# main.net
KiCad netlist of a schematic drawn in EAGLE
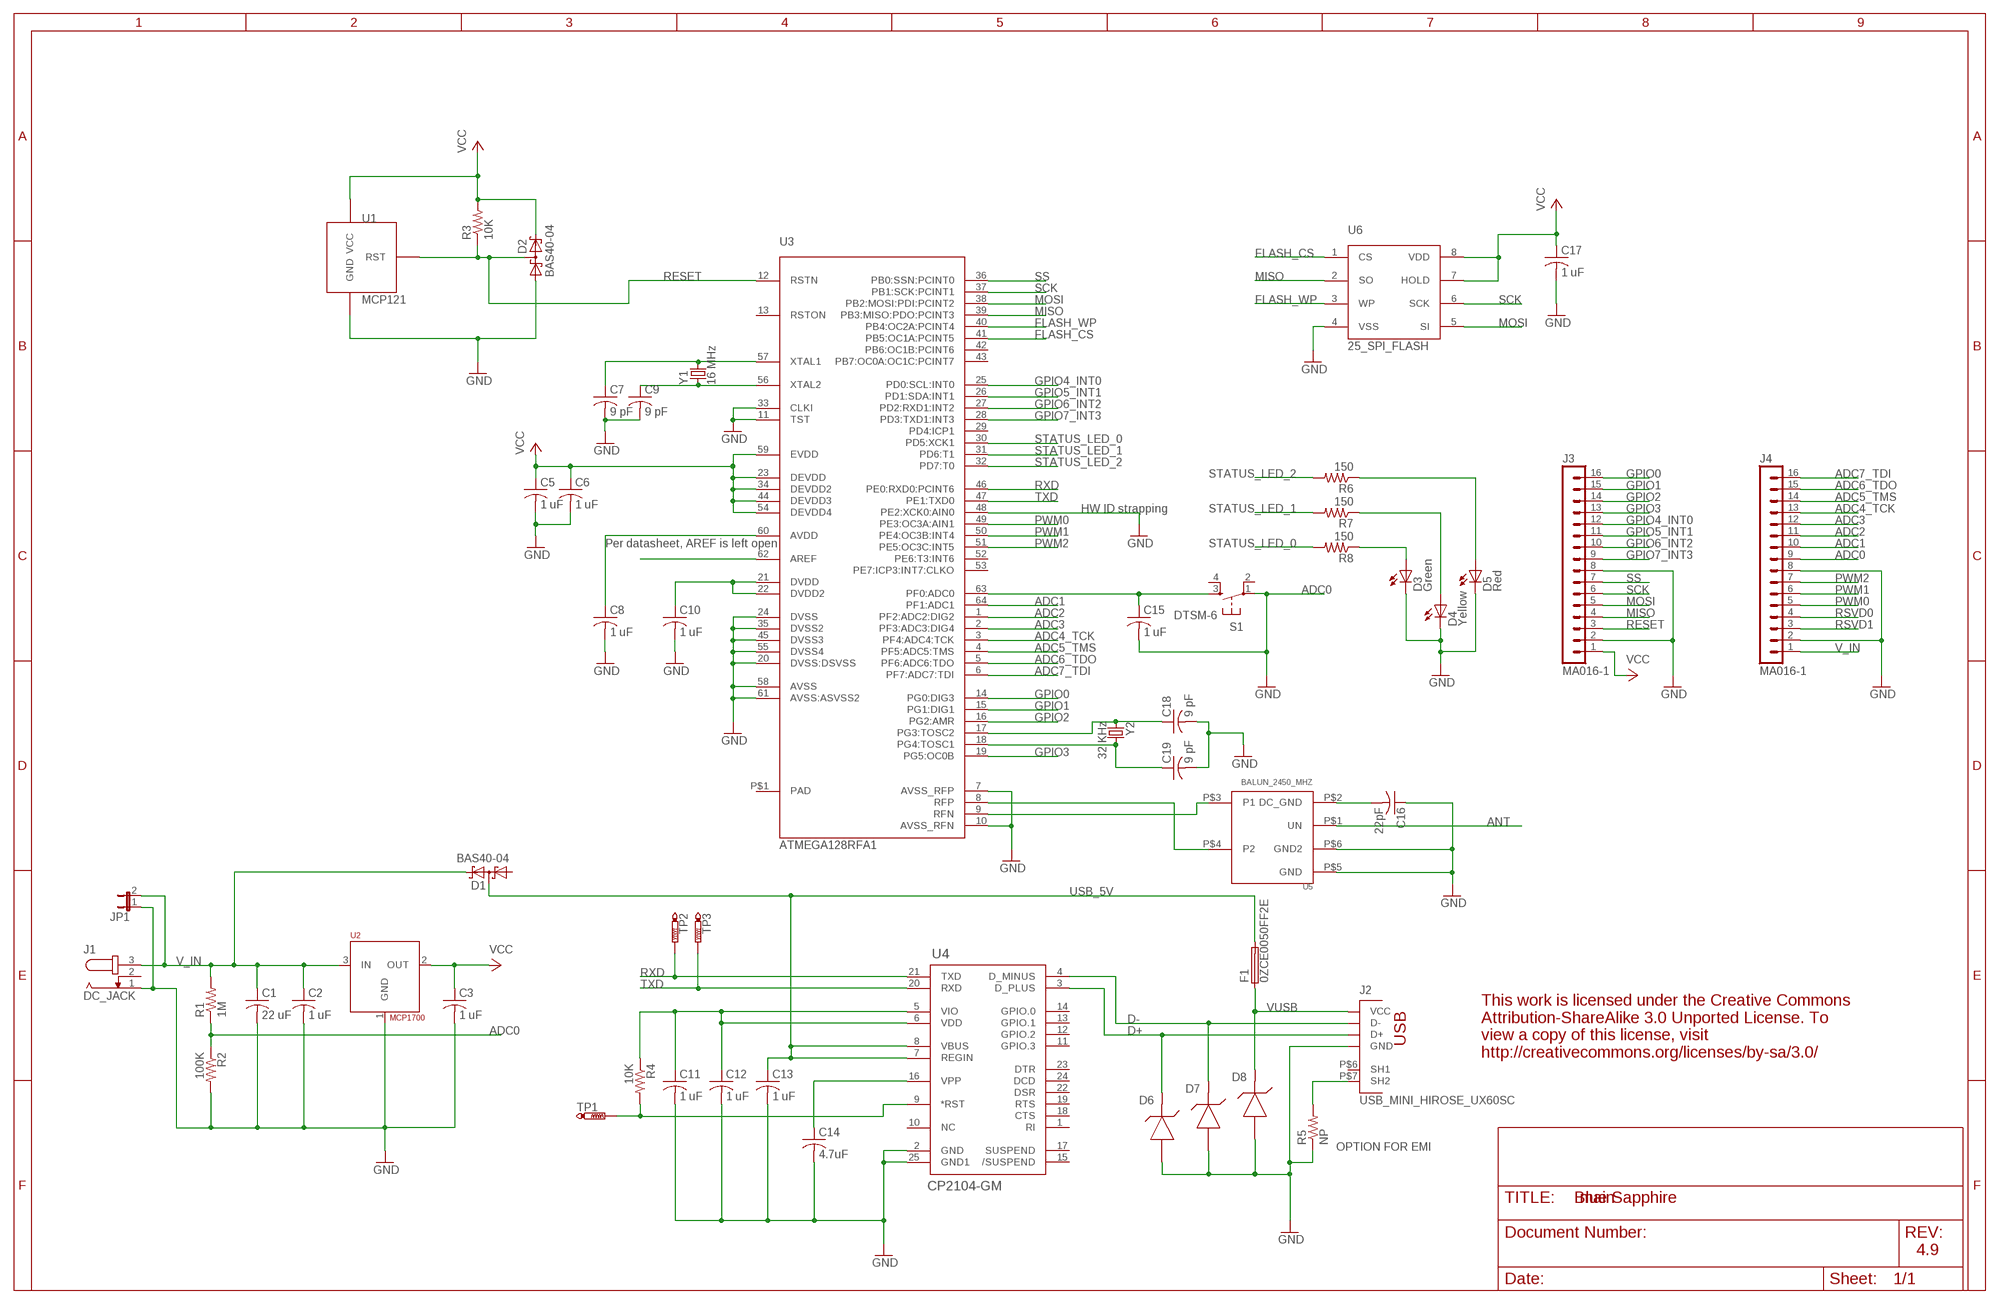
[diagram p0: schematic, sheet 1]

(export (version "E")
  (design (tool "Eeschema 10.0.6"))
  (components
    (comp (ref "C1")
      (value "22 uF")
      (footprint "eagle-import:C0805K")
      (libsource (lib "eagle-import") (part "C-USC0805K"))
    )
    (comp (ref "C2")
      (value "1 uF")
      (footprint "eagle-import:C0603K")
      (libsource (lib "eagle-import") (part "C-USC0603K"))
    )
    (comp (ref "C3")
      (value "1 uF")
      (footprint "eagle-import:C0603K")
      (libsource (lib "eagle-import") (part "C-USC0603K"))
    )
    (comp (ref "C5")
      (value "1 uF")
      (footprint "eagle-import:C0603K")
      (libsource (lib "eagle-import") (part "C-USC0603K"))
    )
    (comp (ref "C6")
      (value "1 uF")
      (footprint "eagle-import:C0603K")
      (libsource (lib "eagle-import") (part "C-USC0603K"))
    )
    (comp (ref "C7")
      (value "9 pF")
      (footprint "eagle-import:C0603K")
      (libsource (lib "eagle-import") (part "C-USC0603K"))
    )
    (comp (ref "C8")
      (value "1 uF")
      (footprint "eagle-import:C0603K")
      (libsource (lib "eagle-import") (part "C-USC0603K"))
    )
    (comp (ref "C9")
      (value "9 pF")
      (footprint "eagle-import:C0603K")
      (libsource (lib "eagle-import") (part "C-USC0603K"))
    )
    (comp (ref "C10")
      (value "1 uF")
      (footprint "eagle-import:C0603K")
      (libsource (lib "eagle-import") (part "C-USC0603K"))
    )
    (comp (ref "C11")
      (value "1 uF")
      (footprint "eagle-import:C0603K")
      (libsource (lib "eagle-import") (part "C-USC0603K"))
    )
    (comp (ref "C12")
      (value "1 uF")
      (footprint "eagle-import:C0603K")
      (libsource (lib "eagle-import") (part "C-USC0603K"))
    )
    (comp (ref "C13")
      (value "1 uF")
      (footprint "eagle-import:C0603K")
      (libsource (lib "eagle-import") (part "C-USC0603K"))
    )
    (comp (ref "C14")
      (value "4.7uF")
      (footprint "eagle-import:C0805K")
      (libsource (lib "eagle-import") (part "C-USC0805K"))
    )
    (comp (ref "C15")
      (value "1 uF")
      (footprint "eagle-import:C0603K")
      (libsource (lib "eagle-import") (part "C-USC0603K"))
    )
    (comp (ref "C16")
      (value "22pF")
      (footprint "eagle-import:C0603K")
      (libsource (lib "eagle-import") (part "C-USC0603K"))
    )
    (comp (ref "C17")
      (value "1 uF")
      (footprint "eagle-import:C0603K")
      (libsource (lib "eagle-import") (part "C-USC0603K"))
    )
    (comp (ref "C18")
      (value "9 pF")
      (footprint "eagle-import:C0603K")
      (libsource (lib "eagle-import") (part "C-USC0603K"))
    )
    (comp (ref "C19")
      (value "9 pF")
      (footprint "eagle-import:C0603K")
      (libsource (lib "eagle-import") (part "C-USC0603K"))
    )
    (comp (ref "D1")
      (value "BAS40-04")
      (footprint "eagle-import:SOT23")
      (libsource (lib "eagle-import") (part "BAS40-04"))
    )
    (comp (ref "D2")
      (value "BAS40-04")
      (footprint "eagle-import:SOT23")
      (libsource (lib "eagle-import") (part "BAS40-04"))
    )
    (comp (ref "D3")
      (value "Green")
      (footprint "eagle-import:CHIPLED_0805")
      (libsource (lib "eagle-import") (part "LEDCHIPLED_0805"))
    )
    (comp (ref "D4")
      (value "Yellow")
      (footprint "eagle-import:CHIPLED_0805")
      (libsource (lib "eagle-import") (part "LEDCHIPLED_0805"))
    )
    (comp (ref "D5")
      (value "Red")
      (footprint "eagle-import:CHIPLED_0805")
      (libsource (lib "eagle-import") (part "LEDCHIPLED_0805"))
    )
    (comp (ref "D6")
      (value "CG0603MLC")
      (footprint "eagle-import:C0603")
      (libsource (lib "eagle-import") (part "CG0603MLC"))
    )
    (comp (ref "D7")
      (value "CG0603MLC")
      (footprint "eagle-import:C0603")
      (libsource (lib "eagle-import") (part "CG0603MLC"))
    )
    (comp (ref "D8")
      (value "CG0603MLC")
      (footprint "eagle-import:C0603")
      (libsource (lib "eagle-import") (part "CG0603MLC"))
    )
    (comp (ref "F1")
      (value "0ZCE0050FF2E")
      (footprint "eagle-import:C0805")
      (libsource (lib "eagle-import") (part "0ZCE0050FF2E"))
    )
    (comp (ref "J1")
      (value "DC_JACK")
      (footprint "eagle-import:CONN_DC_JACK")
      (libsource (lib "eagle-import") (part "DC_JACK"))
    )
    (comp (ref "J2")
      (value "USB_MINI_HIROSE_UX60SC")
      (footprint "eagle-import:USB-MINI-B_HIROSE_UX60SC")
      (libsource (lib "eagle-import") (part "USB_MINI_HIROSE_UX60SC"))
    )
    (comp (ref "J3")
      (value "MA016-1")
      (footprint "eagle-import:MA016-1")
      (libsource (lib "eagle-import") (part "MA016-1"))
    )
    (comp (ref "J4")
      (value "MA016-1")
      (footprint "eagle-import:MA016-1")
      (libsource (lib "eagle-import") (part "MA016-1"))
    )
    (comp (ref "JP1")
      (value "JP1E")
      (footprint "eagle-import:JP1")
      (libsource (lib "eagle-import") (part "JP1E"))
    )
    (comp (ref "R1")
      (value "1M")
      (footprint "eagle-import:R0603")
      (libsource (lib "eagle-import") (part "R-US_R0603"))
    )
    (comp (ref "R2")
      (value "100K")
      (footprint "eagle-import:R0603")
      (libsource (lib "eagle-import") (part "R-US_R0603"))
    )
    (comp (ref "R3")
      (value "10K")
      (footprint "eagle-import:R0603")
      (libsource (lib "eagle-import") (part "R-US_R0603"))
    )
    (comp (ref "R4")
      (value "10K")
      (footprint "eagle-import:R0603")
      (libsource (lib "eagle-import") (part "R-US_R0603"))
    )
    (comp (ref "R5")
      (value "NP")
      (footprint "eagle-import:R0603")
      (libsource (lib "eagle-import") (part "R-US_R0603"))
    )
    (comp (ref "R6")
      (value "150")
      (footprint "eagle-import:R0603")
      (libsource (lib "eagle-import") (part "R-US_R0603"))
    )
    (comp (ref "R7")
      (value "150")
      (footprint "eagle-import:R0603")
      (libsource (lib "eagle-import") (part "R-US_R0603"))
    )
    (comp (ref "R8")
      (value "150")
      (footprint "eagle-import:R0603")
      (libsource (lib "eagle-import") (part "R-US_R0603"))
    )
    (comp (ref "S1")
      (value "DTSM-6")
      (footprint "eagle-import:DTSM-6")
      (libsource (lib "eagle-import") (part "DTSM-6"))
    )
    (comp (ref "TP1")
      (value "PTR1B1,27")
      (footprint "eagle-import:B1,27")
      (libsource (lib "eagle-import") (part "PTR1B1,27"))
    )
    (comp (ref "TP2")
      (value "PTR1B1,27")
      (footprint "eagle-import:B1,27")
      (libsource (lib "eagle-import") (part "PTR1B1,27"))
    )
    (comp (ref "TP3")
      (value "PTR1B1,27")
      (footprint "eagle-import:B1,27")
      (libsource (lib "eagle-import") (part "PTR1B1,27"))
    )
    (comp (ref "U1")
      (value "MCP121")
      (footprint "eagle-import:SOT23")
      (libsource (lib "eagle-import") (part "MCP121"))
    )
    (comp (ref "U2")
      (value "MCP1700")
      (footprint "eagle-import:SOT23")
      (libsource (lib "eagle-import") (part "MCP1700"))
    )
    (comp (ref "U3")
      (value "ATMEGA128RFA1")
      (footprint "eagle-import:MLF64")
      (libsource (lib "eagle-import") (part "ATMEGA128RFA1"))
    )
    (comp (ref "U4")
      (value "CP2104-GM")
      (footprint "eagle-import:QFN24_4X4")
      (libsource (lib "eagle-import") (part "CP2104-GM"))
    )
    (comp (ref "U5")
      (value "BALUN_2450_MHZ")
      (footprint "eagle-import:BALUN_0805")
      (libsource (lib "eagle-import") (part "BALUN_2450_MHZ"))
    )
    (comp (ref "U6")
      (value "25_SPI_FLASH")
      (footprint "eagle-import:SO-8WIDE")
      (libsource (lib "eagle-import") (part "25_SPI_FLASH"))
    )
    (comp (ref "Y1")
      (value "16 MHz")
      (footprint "eagle-import:XTAL_3.2X2.5")
      (libsource (lib "eagle-import") (part "CRYSTAL_3.2X2.5"))
    )
    (comp (ref "Y2")
      (value "32 KHz")
      (footprint "eagle-import:XTAL_3.2X1.5")
      (libsource (lib "eagle-import") (part "CRYSTAL_3.2X1.5"))
    )
  )
  (nets
    (net (code "1") (name "/ADC0") (class "Default")
      (node (ref "C15") (pin "1") (pinfunction "1_1") (pintype "passive"))
      (node (ref "J4") (pin "9") (pinfunction "9_9") (pintype "passive"))
      (node (ref "R1") (pin "1") (pinfunction "1_1") (pintype "passive"))
      (node (ref "R2") (pin "1") (pinfunction "1_1") (pintype "passive"))
      (node (ref "S1") (pin "3") (pinfunction "3_3") (pintype "passive"))
      (node (ref "U3") (pin "63") (pinfunction "PF0:ADC0_63") (pintype "bidirectional"))
    )
    (net (code "2") (name "/ADC1") (class "Default")
      (node (ref "J4") (pin "10") (pinfunction "10_10") (pintype "passive"))
      (node (ref "U3") (pin "64") (pinfunction "PF1:ADC1_64") (pintype "bidirectional"))
    )
    (net (code "3") (name "/ADC2") (class "Default")
      (node (ref "J4") (pin "11") (pinfunction "11_11") (pintype "passive"))
      (node (ref "U3") (pin "1") (pinfunction "PF2:ADC2:DIG2_1") (pintype "bidirectional"))
    )
    (net (code "4") (name "/ADC3") (class "Default")
      (node (ref "J4") (pin "12") (pinfunction "12_12") (pintype "passive"))
      (node (ref "U3") (pin "2") (pinfunction "PF3:ADC3:DIG4_2") (pintype "bidirectional"))
    )
    (net (code "5") (name "/ADC4_TCK") (class "Default")
      (node (ref "J4") (pin "13") (pinfunction "13_13") (pintype "passive"))
      (node (ref "U3") (pin "3") (pinfunction "PF4:ADC4:TCK_3") (pintype "bidirectional"))
    )
    (net (code "6") (name "/ADC5_TMS") (class "Default")
      (node (ref "J4") (pin "14") (pinfunction "14_14") (pintype "passive"))
      (node (ref "U3") (pin "4") (pinfunction "PF5:ADC5:TMS_4") (pintype "bidirectional"))
    )
    (net (code "7") (name "/ADC6_TDO") (class "Default")
      (node (ref "J4") (pin "15") (pinfunction "15_15") (pintype "passive"))
      (node (ref "U3") (pin "5") (pinfunction "PF6:ADC6:TDO_5") (pintype "bidirectional"))
    )
    (net (code "8") (name "/ADC7_TDI") (class "Default")
      (node (ref "J4") (pin "16") (pinfunction "16_16") (pintype "passive"))
      (node (ref "U3") (pin "6") (pinfunction "PF7:ADC7:TDI_6") (pintype "bidirectional"))
    )
    (net (code "9") (name "/ANT") (class "Default")
      (node (ref "U5") (pin "P$1") (pinfunction "UN_P$1") (pintype "bidirectional"))
    )
    (net (code "10") (name "/D+") (class "Default")
      (node (ref "D6") (pin "2") (pinfunction "LINE_2") (pintype "bidirectional"))
      (node (ref "J2") (pin "P$3") (pinfunction "D+_P$3") (pintype "bidirectional"))
      (node (ref "U4") (pin "3") (pinfunction "D_PLUS_3") (pintype "passive"))
    )
    (net (code "11") (name "/D-") (class "Default")
      (node (ref "D7") (pin "2") (pinfunction "LINE_2") (pintype "bidirectional"))
      (node (ref "J2") (pin "P$2") (pinfunction "D-_P$2") (pintype "bidirectional"))
      (node (ref "U4") (pin "4") (pinfunction "D_MINUS_4") (pintype "passive"))
    )
    (net (code "12") (name "/FLASH_CS") (class "Default")
      (node (ref "U3") (pin "41") (pinfunction "PB5:OC1A:PCINT5_41") (pintype "bidirectional"))
      (node (ref "U6") (pin "1") (pinfunction "CS_1") (pintype "bidirectional"))
    )
    (net (code "13") (name "/FLASH_WP") (class "Default")
      (node (ref "U3") (pin "40") (pinfunction "PB4:OC2A:PCINT4_40") (pintype "bidirectional"))
      (node (ref "U6") (pin "3") (pinfunction "WP_3") (pintype "bidirectional"))
    )
    (net (code "14") (name "/GPIO0") (class "Default")
      (node (ref "J3") (pin "16") (pinfunction "16_16") (pintype "passive"))
      (node (ref "U3") (pin "14") (pinfunction "PG0:DIG3_14") (pintype "bidirectional"))
    )
    (net (code "15") (name "/GPIO1") (class "Default")
      (node (ref "J3") (pin "15") (pinfunction "15_15") (pintype "passive"))
      (node (ref "U3") (pin "15") (pinfunction "PG1:DIG1_15") (pintype "bidirectional"))
    )
    (net (code "16") (name "/GPIO2") (class "Default")
      (node (ref "J3") (pin "14") (pinfunction "14_14") (pintype "passive"))
      (node (ref "U3") (pin "16") (pinfunction "PG2:AMR_16") (pintype "bidirectional"))
    )
    (net (code "17") (name "/GPIO3") (class "Default")
      (node (ref "J3") (pin "13") (pinfunction "13_13") (pintype "passive"))
      (node (ref "U3") (pin "19") (pinfunction "PG5:OC0B_19") (pintype "bidirectional"))
    )
    (net (code "18") (name "/GPIO4_INT0") (class "Default")
      (node (ref "J3") (pin "12") (pinfunction "12_12") (pintype "passive"))
      (node (ref "U3") (pin "25") (pinfunction "PD0:SCL:INT0_25") (pintype "bidirectional"))
    )
    (net (code "19") (name "/GPIO5_INT1") (class "Default")
      (node (ref "J3") (pin "11") (pinfunction "11_11") (pintype "passive"))
      (node (ref "U3") (pin "26") (pinfunction "PD1:SDA:INT1_26") (pintype "bidirectional"))
    )
    (net (code "20") (name "/GPIO6_INT2") (class "Default")
      (node (ref "J3") (pin "10") (pinfunction "10_10") (pintype "passive"))
      (node (ref "U3") (pin "27") (pinfunction "PD2:RXD1:INT2_27") (pintype "bidirectional"))
    )
    (net (code "21") (name "/GPIO7_INT3") (class "Default")
      (node (ref "J3") (pin "9") (pinfunction "9_9") (pintype "passive"))
      (node (ref "U3") (pin "28") (pinfunction "PD3:TXD1:INT3_28") (pintype "bidirectional"))
    )
    (net (code "22") (name "/MISO") (class "Default")
      (node (ref "J3") (pin "4") (pinfunction "4_4") (pintype "passive"))
      (node (ref "U3") (pin "39") (pinfunction "PB3:MISO:PDO:PCINT3_39") (pintype "bidirectional"))
      (node (ref "U6") (pin "2") (pinfunction "SO_2") (pintype "bidirectional"))
    )
    (net (code "23") (name "/MOSI") (class "Default")
      (node (ref "J3") (pin "5") (pinfunction "5_5") (pintype "passive"))
      (node (ref "U3") (pin "38") (pinfunction "PB2:MOSI:PDI:PCINT2_38") (pintype "bidirectional"))
      (node (ref "U6") (pin "5") (pinfunction "SI_5") (pintype "bidirectional"))
    )
    (net (code "24") (name "/PWM0") (class "Default")
      (node (ref "J4") (pin "5") (pinfunction "5_5") (pintype "passive"))
      (node (ref "U3") (pin "49") (pinfunction "PE3:OC3A:AIN1_49") (pintype "bidirectional"))
    )
    (net (code "25") (name "/PWM1") (class "Default")
      (node (ref "J4") (pin "6") (pinfunction "6_6") (pintype "passive"))
      (node (ref "U3") (pin "50") (pinfunction "PE4:OC3B:INT4_50") (pintype "bidirectional"))
    )
    (net (code "26") (name "/PWM2") (class "Default")
      (node (ref "J4") (pin "7") (pinfunction "7_7") (pintype "passive"))
      (node (ref "U3") (pin "51") (pinfunction "PE5:OC3C:INT5_51") (pintype "bidirectional"))
    )
    (net (code "27") (name "/RESET") (class "Default")
      (node (ref "D2") (pin "3") (pinfunction "C1A2_3") (pintype "passive"))
      (node (ref "J3") (pin "3") (pinfunction "3_3") (pintype "passive"))
      (node (ref "R3") (pin "1") (pinfunction "1_1") (pintype "passive"))
      (node (ref "U1") (pin "1") (pinfunction "RST_1") (pintype "bidirectional"))
      (node (ref "U3") (pin "12") (pinfunction "RSTN_12") (pintype "bidirectional"))
    )
    (net (code "28") (name "/RSVD0") (class "Default")
      (node (ref "J4") (pin "4") (pinfunction "4_4") (pintype "passive"))
    )
    (net (code "29") (name "/RSVD1") (class "Default")
      (node (ref "J4") (pin "3") (pinfunction "3_3") (pintype "passive"))
    )
    (net (code "30") (name "/RXD") (class "Default")
      (node (ref "TP2") (pin "TP") (pinfunction "TP_TP") (pintype "input"))
      (node (ref "U3") (pin "46") (pinfunction "PE0:RXD0:PCINT6_46") (pintype "bidirectional"))
      (node (ref "U4") (pin "21") (pinfunction "TXD_21") (pintype "output"))
    )
    (net (code "31") (name "/SCK") (class "Default")
      (node (ref "J3") (pin "6") (pinfunction "6_6") (pintype "passive"))
      (node (ref "U3") (pin "37") (pinfunction "PB1:SCK:PCINT1_37") (pintype "bidirectional"))
      (node (ref "U6") (pin "6") (pinfunction "SCK_6") (pintype "bidirectional"))
    )
    (net (code "32") (name "/SS") (class "Default")
      (node (ref "J3") (pin "7") (pinfunction "7_7") (pintype "passive"))
      (node (ref "U3") (pin "36") (pinfunction "PB0:SSN:PCINT0_36") (pintype "bidirectional"))
    )
    (net (code "33") (name "/STATUS_LED_0") (class "Default")
      (node (ref "R8") (pin "2") (pinfunction "2_2") (pintype "passive"))
      (node (ref "U3") (pin "30") (pinfunction "PD5:XCK1_30") (pintype "bidirectional"))
    )
    (net (code "34") (name "/STATUS_LED_1") (class "Default")
      (node (ref "R7") (pin "2") (pinfunction "2_2") (pintype "passive"))
      (node (ref "U3") (pin "31") (pinfunction "PD6:T1_31") (pintype "bidirectional"))
    )
    (net (code "35") (name "/STATUS_LED_2") (class "Default")
      (node (ref "R6") (pin "2") (pinfunction "2_2") (pintype "passive"))
      (node (ref "U3") (pin "32") (pinfunction "PD7:T0_32") (pintype "bidirectional"))
    )
    (net (code "36") (name "/TXD") (class "Default")
      (node (ref "TP3") (pin "TP") (pinfunction "TP_TP") (pintype "input"))
      (node (ref "U3") (pin "47") (pinfunction "PE1:TXD0_47") (pintype "bidirectional"))
      (node (ref "U4") (pin "20") (pinfunction "RXD_20") (pintype "input"))
    )
    (net (code "37") (name "/USB_5V") (class "Default")
      (node (ref "C13") (pin "1") (pinfunction "1_1") (pintype "passive"))
      (node (ref "D1") (pin "3") (pinfunction "C1A2_3") (pintype "passive"))
      (node (ref "F1") (pin "2") (pinfunction "2_2") (pintype "passive"))
      (node (ref "U4") (pin "7") (pinfunction "REGIN_7") (pintype "input"))
      (node (ref "U4") (pin "8") (pinfunction "VBUS_8") (pintype "input"))
    )
    (net (code "38") (name "/VUSB") (class "Default")
      (node (ref "D8") (pin "2") (pinfunction "LINE_2") (pintype "bidirectional"))
      (node (ref "F1") (pin "1") (pinfunction "1_1") (pintype "passive"))
      (node (ref "J2") (pin "P$1") (pinfunction "VCC_P$1") (pintype "bidirectional"))
    )
    (net (code "39") (name "/V_IN") (class "Default")
      (node (ref "C1") (pin "1") (pinfunction "1_1") (pintype "passive"))
      (node (ref "C2") (pin "1") (pinfunction "1_1") (pintype "passive"))
      (node (ref "D1") (pin "2") (pinfunction "C2_2") (pintype "passive"))
      (node (ref "J1") (pin "3") (pinfunction "3_3") (pintype "passive"))
      (node (ref "J4") (pin "1") (pinfunction "1_1") (pintype "passive"))
      (node (ref "JP1") (pin "2") (pinfunction "2_2") (pintype "passive"))
      (node (ref "R1") (pin "2") (pinfunction "2_2") (pintype "passive"))
      (node (ref "U2") (pin "3") (pinfunction "IN_3") (pintype "bidirectional"))
    )
    (net (code "40") (name "GND") (class "Default")
      (node (ref "C1") (pin "2") (pinfunction "2_2") (pintype "passive"))
      (node (ref "C10") (pin "2") (pinfunction "2_2") (pintype "passive"))
      (node (ref "C11") (pin "2") (pinfunction "2_2") (pintype "passive"))
      (node (ref "C12") (pin "2") (pinfunction "2_2") (pintype "passive"))
      (node (ref "C13") (pin "2") (pinfunction "2_2") (pintype "passive"))
      (node (ref "C14") (pin "2") (pinfunction "2_2") (pintype "passive"))
      (node (ref "C15") (pin "2") (pinfunction "2_2") (pintype "passive"))
      (node (ref "C16") (pin "1") (pinfunction "1_1") (pintype "passive"))
      (node (ref "C17") (pin "2") (pinfunction "2_2") (pintype "passive"))
      (node (ref "C18") (pin "2") (pinfunction "2_2") (pintype "passive"))
      (node (ref "C19") (pin "2") (pinfunction "2_2") (pintype "passive"))
      (node (ref "C2") (pin "2") (pinfunction "2_2") (pintype "passive"))
      (node (ref "C3") (pin "2") (pinfunction "2_2") (pintype "passive"))
      (node (ref "C5") (pin "2") (pinfunction "2_2") (pintype "passive"))
      (node (ref "C6") (pin "2") (pinfunction "2_2") (pintype "passive"))
      (node (ref "C7") (pin "2") (pinfunction "2_2") (pintype "passive"))
      (node (ref "C8") (pin "2") (pinfunction "2_2") (pintype "passive"))
      (node (ref "C9") (pin "2") (pinfunction "2_2") (pintype "passive"))
      (node (ref "D2") (pin "1") (pinfunction "A1_1") (pintype "passive"))
      (node (ref "D3") (pin "C") (pinfunction "C_C") (pintype "passive"))
      (node (ref "D4") (pin "C") (pinfunction "C_C") (pintype "passive"))
      (node (ref "D5") (pin "C") (pinfunction "C_C") (pintype "passive"))
      (node (ref "D6") (pin "1") (pinfunction "GND_1") (pintype "bidirectional"))
      (node (ref "D7") (pin "1") (pinfunction "GND_1") (pintype "bidirectional"))
      (node (ref "D8") (pin "1") (pinfunction "GND_1") (pintype "bidirectional"))
      (node (ref "J1") (pin "1") (pinfunction "1_1") (pintype "passive"))
      (node (ref "J2") (pin "P$5") (pinfunction "GND_P$5") (pintype "bidirectional"))
      (node (ref "J3") (pin "2") (pinfunction "2_2") (pintype "passive"))
      (node (ref "J3") (pin "8") (pinfunction "8_8") (pintype "passive"))
      (node (ref "J4") (pin "2") (pinfunction "2_2") (pintype "passive"))
      (node (ref "J4") (pin "8") (pinfunction "8_8") (pintype "passive"))
      (node (ref "JP1") (pin "1") (pinfunction "1_1") (pintype "passive"))
      (node (ref "R2") (pin "2") (pinfunction "2_2") (pintype "passive"))
      (node (ref "R5") (pin "1") (pinfunction "1_1") (pintype "passive"))
      (node (ref "S1") (pin "1") (pinfunction "1_1") (pintype "passive"))
      (node (ref "U1") (pin "3") (pinfunction "GND_3") (pintype "bidirectional"))
      (node (ref "U2") (pin "1") (pinfunction "GND_1") (pintype "bidirectional"))
      (node (ref "U3") (pin "10") (pinfunction "AVSS_RFN_10") (pintype "bidirectional"))
      (node (ref "U3") (pin "11") (pinfunction "TST_11") (pintype "bidirectional"))
      (node (ref "U3") (pin "20") (pinfunction "DVSS:DSVSS_20") (pintype "bidirectional"))
      (node (ref "U3") (pin "24") (pinfunction "DVSS_24") (pintype "bidirectional"))
      (node (ref "U3") (pin "33") (pinfunction "CLKI_33") (pintype "bidirectional"))
      (node (ref "U3") (pin "35") (pinfunction "DVSS2_35") (pintype "bidirectional"))
      (node (ref "U3") (pin "45") (pinfunction "DVSS3_45") (pintype "bidirectional"))
      (node (ref "U3") (pin "48") (pinfunction "PE2:XCK0:AIN0_48") (pintype "bidirectional"))
      (node (ref "U3") (pin "55") (pinfunction "DVSS4_55") (pintype "bidirectional"))
      (node (ref "U3") (pin "58") (pinfunction "AVSS_58") (pintype "bidirectional"))
      (node (ref "U3") (pin "61") (pinfunction "AVSS:ASVSS2_61") (pintype "bidirectional"))
      (node (ref "U3") (pin "7") (pinfunction "AVSS_RFP_7") (pintype "bidirectional"))
      (node (ref "U4") (pin "2") (pinfunction "GND_2") (pintype "power_in"))
      (node (ref "U4") (pin "25") (pinfunction "GND1_25") (pintype "passive"))
      (node (ref "U5") (pin "P$5") (pinfunction "GND_P$5") (pintype "bidirectional"))
      (node (ref "U5") (pin "P$6") (pinfunction "GND2_P$6") (pintype "bidirectional"))
      (node (ref "U6") (pin "4") (pinfunction "VSS_4") (pintype "bidirectional"))
    )
    (net (code "41") (name "Net-(D3-PadA)") (class "Default")
      (node (ref "D3") (pin "A") (pinfunction "A_A") (pintype "passive"))
      (node (ref "R8") (pin "1") (pinfunction "1_1") (pintype "passive"))
    )
    (net (code "42") (name "Net-(D4-PadA)") (class "Default")
      (node (ref "D4") (pin "A") (pinfunction "A_A") (pintype "passive"))
      (node (ref "R7") (pin "1") (pinfunction "1_1") (pintype "passive"))
    )
    (net (code "43") (name "Net-(D5-PadA)") (class "Default")
      (node (ref "D5") (pin "A") (pinfunction "A_A") (pintype "passive"))
      (node (ref "R6") (pin "1") (pinfunction "1_1") (pintype "passive"))
    )
    (net (code "44") (name "Net-(J2-SH2)") (class "Default")
      (node (ref "J2") (pin "P$7") (pinfunction "SH2_P$7") (pintype "bidirectional"))
      (node (ref "R5") (pin "2") (pinfunction "2_2") (pintype "passive"))
    )
    (net (code "45") (name "Net-(U3-AVDD)") (class "Default")
      (node (ref "C8") (pin "1") (pinfunction "1_1") (pintype "passive"))
      (node (ref "U3") (pin "60") (pinfunction "AVDD_60") (pintype "bidirectional"))
    )
    (net (code "46") (name "Net-(U3-DVDD)") (class "Default")
      (node (ref "C10") (pin "1") (pinfunction "1_1") (pintype "passive"))
      (node (ref "U3") (pin "21") (pinfunction "DVDD_21") (pintype "bidirectional"))
      (node (ref "U3") (pin "22") (pinfunction "DVDD2_22") (pintype "bidirectional"))
    )
    (net (code "47") (name "Net-(U3-PG3:TOSC2)") (class "Default")
      (node (ref "C18") (pin "1") (pinfunction "1_1") (pintype "passive"))
      (node (ref "U3") (pin "17") (pinfunction "PG3:TOSC2_17") (pintype "bidirectional"))
      (node (ref "Y2") (pin "P$1") (pinfunction "1_P$1") (pintype "passive"))
    )
    (net (code "48") (name "Net-(U3-PG4:TOSC1)") (class "Default")
      (node (ref "C19") (pin "1") (pinfunction "1_1") (pintype "passive"))
      (node (ref "U3") (pin "18") (pinfunction "PG4:TOSC1_18") (pintype "bidirectional"))
      (node (ref "Y2") (pin "P$2") (pinfunction "2_P$2") (pintype "passive"))
    )
    (net (code "49") (name "Net-(U3-RFN)") (class "Default")
      (node (ref "U3") (pin "9") (pinfunction "RFN_9") (pintype "bidirectional"))
      (node (ref "U5") (pin "P$3") (pinfunction "P1_P$3") (pintype "bidirectional"))
    )
    (net (code "50") (name "Net-(U3-RFP)") (class "Default")
      (node (ref "U3") (pin "8") (pinfunction "RFP_8") (pintype "bidirectional"))
      (node (ref "U5") (pin "P$4") (pinfunction "P2_P$4") (pintype "bidirectional"))
    )
    (net (code "51") (name "Net-(U3-XTAL1)") (class "Default")
      (node (ref "C7") (pin "1") (pinfunction "1_1") (pintype "passive"))
      (node (ref "U3") (pin "57") (pinfunction "XTAL1_57") (pintype "bidirectional"))
      (node (ref "Y1") (pin "P$3") (pinfunction "2_P$3") (pintype "passive"))
    )
    (net (code "52") (name "Net-(U3-XTAL2)") (class "Default")
      (node (ref "C9") (pin "1") (pinfunction "1_1") (pintype "passive"))
      (node (ref "U3") (pin "56") (pinfunction "XTAL2_56") (pintype "bidirectional"))
      (node (ref "Y1") (pin "P$1") (pinfunction "1_P$1") (pintype "passive"))
    )
    (net (code "53") (name "Net-(U4-*RST)") (class "Default")
      (node (ref "R4") (pin "2") (pinfunction "2_2") (pintype "passive"))
      (node (ref "TP1") (pin "TP") (pinfunction "TP_TP") (pintype "input"))
      (node (ref "U4") (pin "9") (pinfunction "*RST_9") (pintype "passive"))
    )
    (net (code "54") (name "Net-(U4-VDD)") (class "Default")
      (node (ref "C11") (pin "1") (pinfunction "1_1") (pintype "passive"))
      (node (ref "C12") (pin "1") (pinfunction "1_1") (pintype "passive"))
      (node (ref "R4") (pin "1") (pinfunction "1_1") (pintype "passive"))
      (node (ref "U4") (pin "5") (pinfunction "VIO_5") (pintype "power_in"))
      (node (ref "U4") (pin "6") (pinfunction "VDD_6") (pintype "power_in"))
    )
    (net (code "55") (name "Net-(U4-VPP)") (class "Default")
      (node (ref "C14") (pin "1") (pinfunction "1_1") (pintype "passive"))
      (node (ref "U4") (pin "16") (pinfunction "VPP_16") (pintype "passive"))
    )
    (net (code "56") (name "Net-(U5-DC_GND)") (class "Default")
      (node (ref "C16") (pin "2") (pinfunction "2_2") (pintype "passive"))
      (node (ref "U5") (pin "P$2") (pinfunction "DC_GND_P$2") (pintype "bidirectional"))
    )
    (net (code "57") (name "VCC") (class "Default")
      (node (ref "C17") (pin "1") (pinfunction "1_1") (pintype "passive"))
      (node (ref "C3") (pin "1") (pinfunction "1_1") (pintype "passive"))
      (node (ref "C5") (pin "1") (pinfunction "1_1") (pintype "passive"))
      (node (ref "C6") (pin "1") (pinfunction "1_1") (pintype "passive"))
      (node (ref "D2") (pin "2") (pinfunction "C2_2") (pintype "passive"))
      (node (ref "J3") (pin "1") (pinfunction "1_1") (pintype "passive"))
      (node (ref "R3") (pin "2") (pinfunction "2_2") (pintype "passive"))
      (node (ref "U1") (pin "2") (pinfunction "VCC_2") (pintype "bidirectional"))
      (node (ref "U2") (pin "2") (pinfunction "OUT_2") (pintype "bidirectional"))
      (node (ref "U3") (pin "23") (pinfunction "DEVDD_23") (pintype "bidirectional"))
      (node (ref "U3") (pin "34") (pinfunction "DEVDD2_34") (pintype "bidirectional"))
      (node (ref "U3") (pin "44") (pinfunction "DEVDD3_44") (pintype "bidirectional"))
      (node (ref "U3") (pin "54") (pinfunction "DEVDD4_54") (pintype "bidirectional"))
      (node (ref "U3") (pin "59") (pinfunction "EVDD_59") (pintype "bidirectional"))
      (node (ref "U6") (pin "7") (pinfunction "HOLD_7") (pintype "bidirectional"))
      (node (ref "U6") (pin "8") (pinfunction "VDD_8") (pintype "bidirectional"))
    )
    (net (code "58") (name "unconnected-(D1-A1-Pad1)") (class "Default")
      (node (ref "D1") (pin "1") (pinfunction "A1_1") (pintype "passive"))
    )
    (net (code "59") (name "unconnected-(J1-Pad2)") (class "Default")
      (node (ref "J1") (pin "2") (pinfunction "2_2") (pintype "passive"))
    )
    (net (code "60") (name "unconnected-(J2-SH1-PadP$6)") (class "Default")
      (node (ref "J2") (pin "P$6") (pinfunction "SH1_P$6") (pintype "bidirectional"))
    )
    (net (code "61") (name "unconnected-(S1-Pad2)") (class "Default")
      (node (ref "S1") (pin "2") (pinfunction "2_2") (pintype "passive"))
    )
    (net (code "62") (name "unconnected-(S1-Pad4)") (class "Default")
      (node (ref "S1") (pin "4") (pinfunction "4_4") (pintype "passive"))
    )
    (net (code "63") (name "unconnected-(U3-AREF-Pad62)") (class "Default")
      (node (ref "U3") (pin "62") (pinfunction "AREF_62") (pintype "bidirectional"))
    )
    (net (code "64") (name "unconnected-(U3-PAD-PadP$1)") (class "Default")
      (node (ref "U3") (pin "P$1") (pinfunction "PAD_P$1") (pintype "bidirectional"))
    )
    (net (code "65") (name "unconnected-(U3-PB6:OC1B:PCINT6-Pad42)") (class "Default")
      (node (ref "U3") (pin "42") (pinfunction "PB6:OC1B:PCINT6_42") (pintype "bidirectional"))
    )
    (net (code "66") (name "unconnected-(U3-PB7:OC0A:OC1C:PCINT7-Pad43)") (class "Default")
      (node (ref "U3") (pin "43") (pinfunction "PB7:OC0A:OC1C:PCINT7_43") (pintype "bidirectional"))
    )
    (net (code "67") (name "unconnected-(U3-PD4:ICP1-Pad29)") (class "Default")
      (node (ref "U3") (pin "29") (pinfunction "PD4:ICP1_29") (pintype "bidirectional"))
    )
    (net (code "68") (name "unconnected-(U3-PE6:T3:INT6-Pad52)") (class "Default")
      (node (ref "U3") (pin "52") (pinfunction "PE6:T3:INT6_52") (pintype "bidirectional"))
    )
    (net (code "69") (name "unconnected-(U3-PE7:ICP3:INT7:CLKO-Pad53)") (class "Default")
      (node (ref "U3") (pin "53") (pinfunction "PE7:ICP3:INT7:CLKO_53") (pintype "bidirectional"))
    )
    (net (code "70") (name "unconnected-(U3-RSTON-Pad13)") (class "Default")
      (node (ref "U3") (pin "13") (pinfunction "RSTON_13") (pintype "bidirectional"))
    )
    (net (code "71") (name "unconnected-(U4-CTS-Pad18)") (class "Default")
      (node (ref "U4") (pin "18") (pinfunction "CTS_18") (pintype "input"))
    )
    (net (code "72") (name "unconnected-(U4-DCD-Pad24)") (class "Default")
      (node (ref "U4") (pin "24") (pinfunction "DCD_24") (pintype "input"))
    )
    (net (code "73") (name "unconnected-(U4-DSR-Pad22)") (class "Default")
      (node (ref "U4") (pin "22") (pinfunction "DSR_22") (pintype "input"))
    )
    (net (code "74") (name "unconnected-(U4-DTR-Pad23)") (class "Default")
      (node (ref "U4") (pin "23") (pinfunction "DTR_23") (pintype "output"))
    )
    (net (code "75") (name "unconnected-(U4-GPIO.0-Pad14)") (class "Default")
      (node (ref "U4") (pin "14") (pinfunction "GPIO.0_14") (pintype "passive"))
    )
    (net (code "76") (name "unconnected-(U4-GPIO.1-Pad13)") (class "Default")
      (node (ref "U4") (pin "13") (pinfunction "GPIO.1_13") (pintype "passive"))
    )
    (net (code "77") (name "unconnected-(U4-GPIO.2-Pad12)") (class "Default")
      (node (ref "U4") (pin "12") (pinfunction "GPIO.2_12") (pintype "passive"))
    )
    (net (code "78") (name "unconnected-(U4-GPIO.3-Pad11)") (class "Default")
      (node (ref "U4") (pin "11") (pinfunction "GPIO.3_11") (pintype "passive"))
    )
    (net (code "79") (name "unconnected-(U4-NC-Pad10)") (class "Default")
      (node (ref "U4") (pin "10") (pinfunction "NC_10") (pintype "no_connect"))
    )
    (net (code "80") (name "unconnected-(U4-RI-Pad1)") (class "Default")
      (node (ref "U4") (pin "1") (pinfunction "RI_1") (pintype "input"))
    )
    (net (code "81") (name "unconnected-(U4-RTS-Pad19)") (class "Default")
      (node (ref "U4") (pin "19") (pinfunction "RTS_19") (pintype "output"))
    )
    (net (code "82") (name "unconnected-(U4-SUSPEND-Pad17)") (class "Default")
      (node (ref "U4") (pin "17") (pinfunction "SUSPEND_17") (pintype "output"))
    )
    (net (code "83") (name "unconnected-(U4-{slash}SUSPEND-Pad15)") (class "Default")
      (node (ref "U4") (pin "15") (pinfunction "/SUSPEND_15") (pintype "output"))
    )
  )
)
